# packmonitor.net
KiCad netlist of a schematic drawn in EAGLE
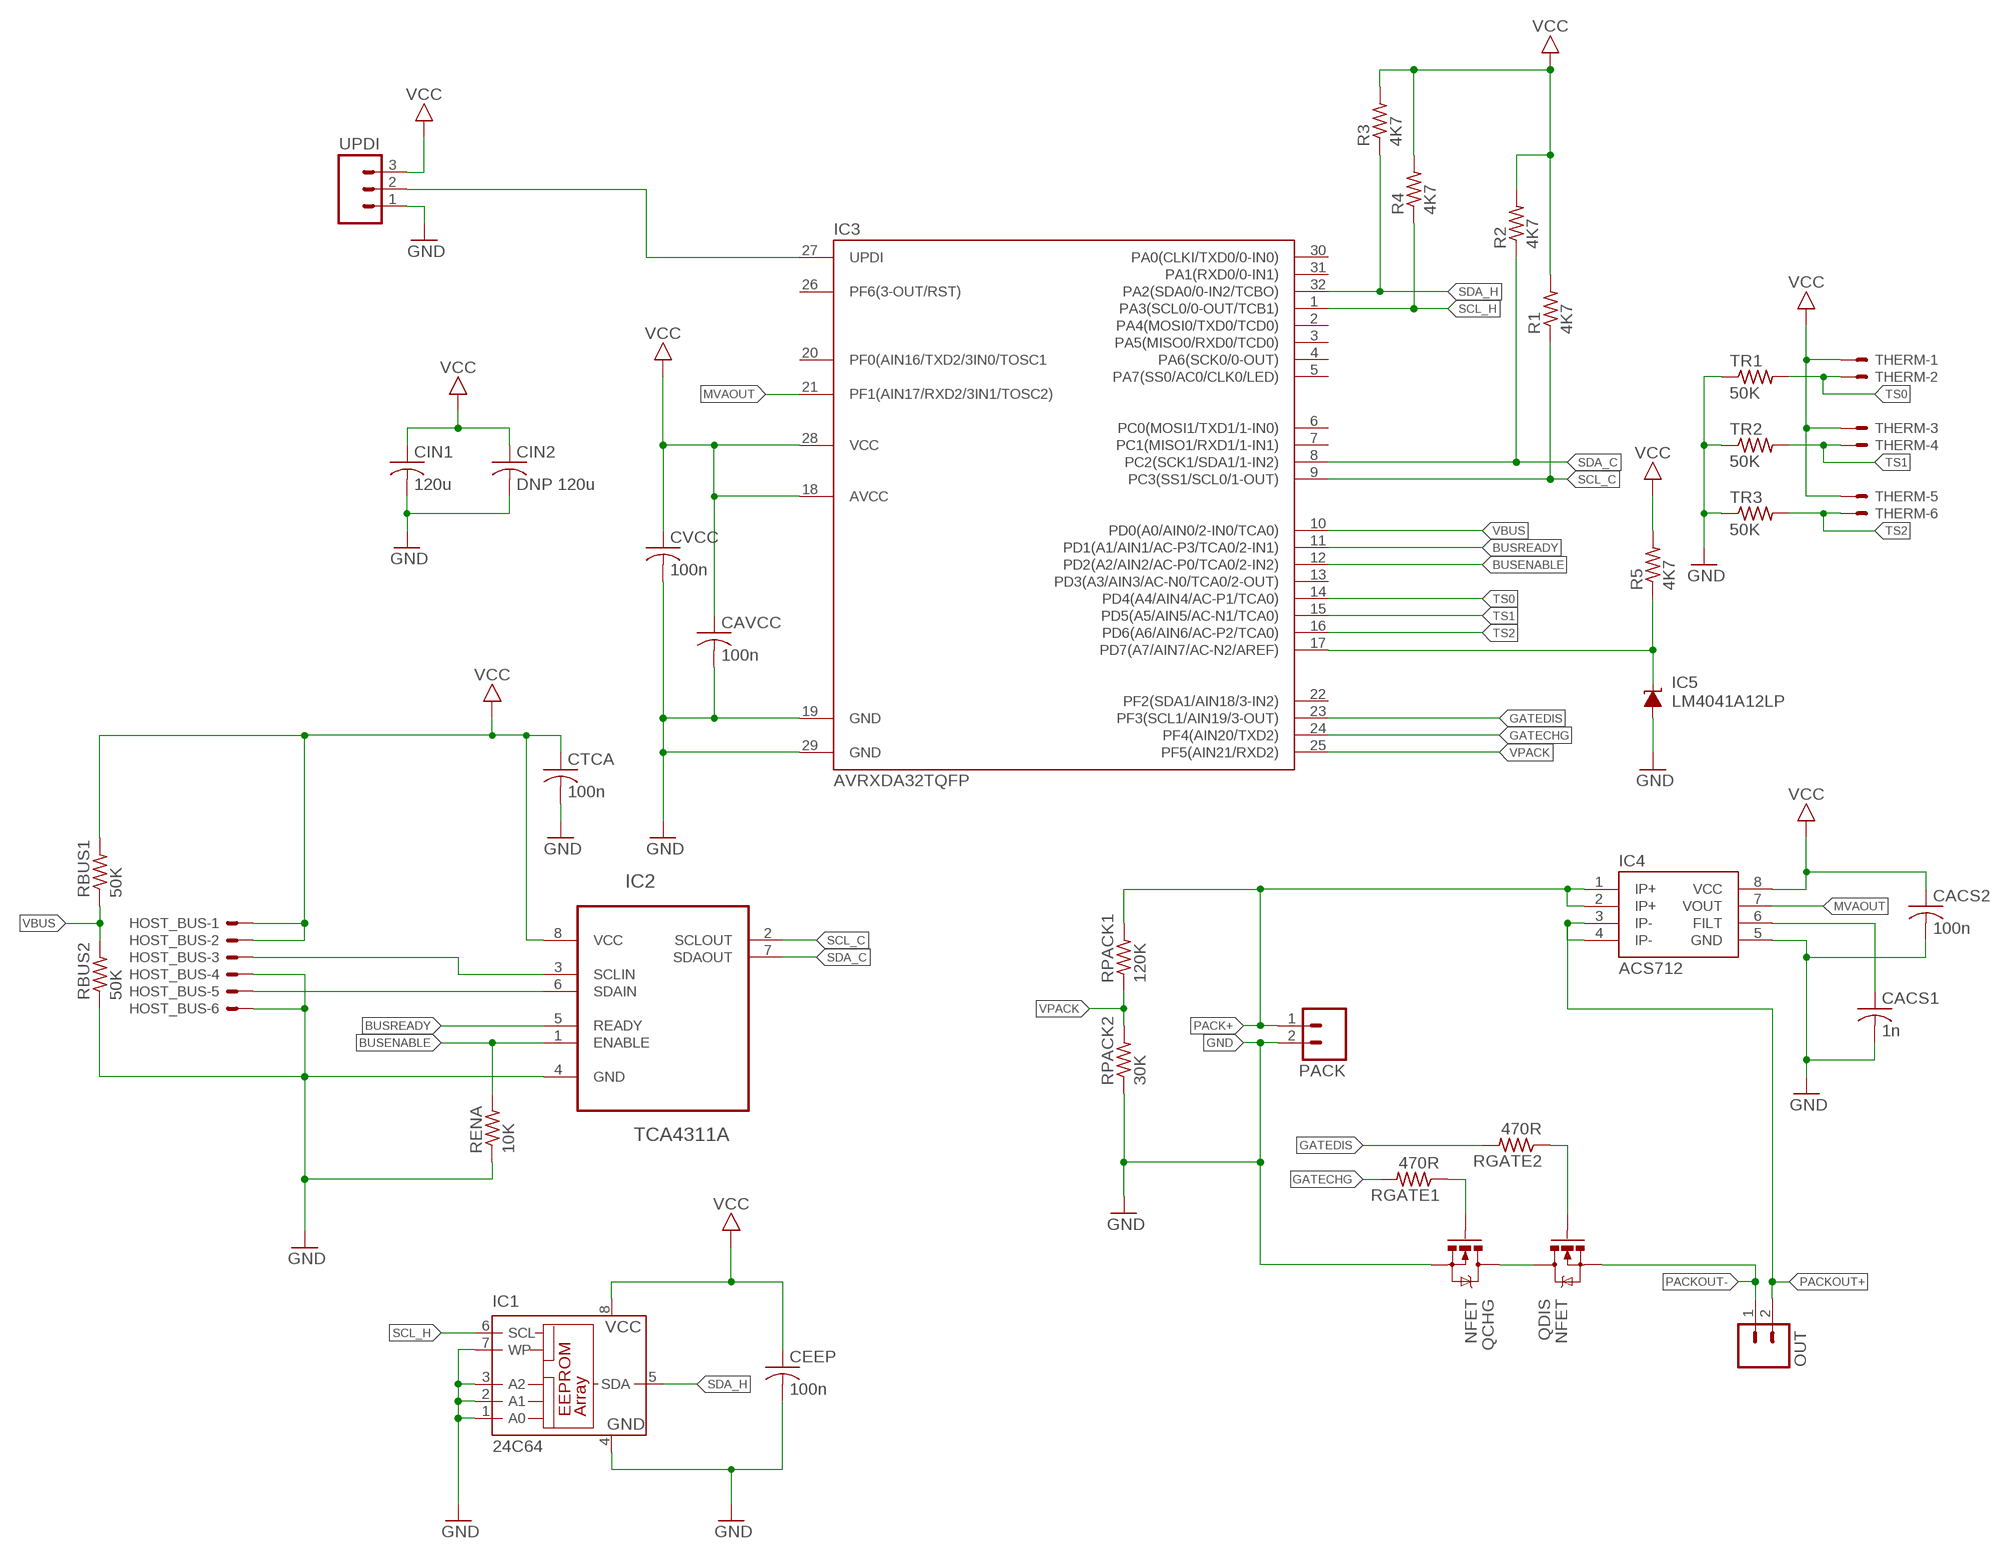
[diagram p0: schematic, sheet 1]

(export (version "E")
  (design (tool "Eeschema 10.0.6"))
  (components
    (comp (ref "CACS1")
      (value "1n")
      (footprint "eagle-import:C0603")
      (libsource (lib "eagle-import") (part "C-USC0603"))
    )
    (comp (ref "CACS2")
      (value "100n")
      (footprint "eagle-import:C0603")
      (libsource (lib "eagle-import") (part "C-USC0603"))
    )
    (comp (ref "CAVCC")
      (value "100n")
      (footprint "eagle-import:C0603")
      (libsource (lib "eagle-import") (part "C-USC0603"))
    )
    (comp (ref "CEEP")
      (value "100n")
      (footprint "eagle-import:C0603")
      (libsource (lib "eagle-import") (part "C-USC0603"))
    )
    (comp (ref "CIN1")
      (value "120u")
      (footprint "eagle-import:C1206")
      (libsource (lib "eagle-import") (part "C-USC1206"))
    )
    (comp (ref "CIN2")
      (value "DNP 120u")
      (footprint "eagle-import:C1206")
      (libsource (lib "eagle-import") (part "C-USC1206"))
    )
    (comp (ref "CTCA")
      (value "100n")
      (footprint "eagle-import:C0603")
      (libsource (lib "eagle-import") (part "C-USC0603"))
    )
    (comp (ref "CVCC")
      (value "100n")
      (footprint "eagle-import:C0603")
      (libsource (lib "eagle-import") (part "C-USC0603"))
    )
    (comp (ref "HOST_BUS")
      (value "JST-XH-06-PIN-LONG-PAD")
      (footprint "eagle-import:JST-XH-06-PACKAGE-LONG-PAD")
      (libsource (lib "eagle-import") (part "JST-XH-06-PIN-LONG-PAD"))
    )
    (comp (ref "IC1")
      (value "24C64")
      (footprint "eagle-import:SO-08")
      (libsource (lib "eagle-import") (part "24CSN04C"))
    )
    (comp (ref "IC2")
      (value "TCA4311A")
      (footprint "eagle-import:SOIC127P600X175-8N")
      (fields (field (name "MPN") "PCA9511AD,118"))
      (libsource (lib "eagle-import") (part "PCA9511AD,118"))
    )
    (comp (ref "IC3")
      (value "AVRXDA32TQFP")
      (footprint "eagle-import:TQFP32-08")
      (libsource (lib "eagle-import") (part "AVRXDA32TQFP"))
    )
    (comp (ref "IC4")
      (value "ACS712")
      (footprint "eagle-import:SO08")
      (libsource (lib "eagle-import") (part "ACS712"))
    )
    (comp (ref "IC5")
      (value "LM4041A12LP")
      (footprint "eagle-import:LP_O-PBCY-W3")
      (libsource (lib "eagle-import") (part "LM4041LPA12"))
    )
    (comp (ref "OUT")
      (value "M023.5MM")
      (footprint "eagle-import:SCREWTERMINAL-3.5MM-2")
      (libsource (lib "eagle-import") (part "M023.5MM"))
    )
    (comp (ref "PACK")
      (value "M023.5MM")
      (footprint "eagle-import:SCREWTERMINAL-3.5MM-2")
      (libsource (lib "eagle-import") (part "M023.5MM"))
    )
    (comp (ref "QCHG")
      (value "NFET")
      (footprint "eagle-import:SO08")
      (libsource (lib "eagle-import") (part "MOSFET-NCHANNELFDS6630A"))
    )
    (comp (ref "QDIS")
      (value "NFET")
      (footprint "eagle-import:SO08")
      (libsource (lib "eagle-import") (part "MOSFET-NCHANNELFDS6630A"))
    )
    (comp (ref "R1")
      (value "4K7")
      (footprint "eagle-import:R0603")
      (libsource (lib "eagle-import") (part "R-US_R0603"))
    )
    (comp (ref "R2")
      (value "4K7")
      (footprint "eagle-import:R0603")
      (libsource (lib "eagle-import") (part "R-US_R0603"))
    )
    (comp (ref "R3")
      (value "4K7")
      (footprint "eagle-import:R0603")
      (libsource (lib "eagle-import") (part "R-US_R0603"))
    )
    (comp (ref "R4")
      (value "4K7")
      (footprint "eagle-import:R0603")
      (libsource (lib "eagle-import") (part "R-US_R0603"))
    )
    (comp (ref "R5")
      (value "4K7")
      (footprint "eagle-import:R0603")
      (libsource (lib "eagle-import") (part "R-US_R0603"))
    )
    (comp (ref "RBUS1")
      (value "50K")
      (footprint "eagle-import:R0805")
      (libsource (lib "eagle-import") (part "R-US_R0805"))
    )
    (comp (ref "RBUS2")
      (value "50K")
      (footprint "eagle-import:R0805")
      (libsource (lib "eagle-import") (part "R-US_R0805"))
    )
    (comp (ref "RENA")
      (value "10K")
      (footprint "eagle-import:R0603")
      (libsource (lib "eagle-import") (part "R-US_R0603"))
    )
    (comp (ref "RGATE1")
      (value "470R")
      (footprint "eagle-import:R0603")
      (libsource (lib "eagle-import") (part "R-US_R0603"))
    )
    (comp (ref "RGATE2")
      (value "470R")
      (footprint "eagle-import:R0603")
      (libsource (lib "eagle-import") (part "R-US_R0603"))
    )
    (comp (ref "RPACK1")
      (value "120K")
      (footprint "eagle-import:R0805")
      (libsource (lib "eagle-import") (part "R-US_R0805"))
    )
    (comp (ref "RPACK2")
      (value "30K")
      (footprint "eagle-import:R0805")
      (libsource (lib "eagle-import") (part "R-US_R0805"))
    )
    (comp (ref "THERM")
      (value "JST-XH-06-PIN-ROUND-PAD")
      (footprint "eagle-import:JST-XH-06-PACKAGE-ROUND-PAD")
      (libsource (lib "eagle-import") (part "JST-XH-06-PIN-ROUND-PAD"))
    )
    (comp (ref "TR1")
      (value "50K")
      (footprint "eagle-import:R0805")
      (libsource (lib "eagle-import") (part "R-US_R0805"))
    )
    (comp (ref "TR2")
      (value "50K")
      (footprint "eagle-import:R0805")
      (libsource (lib "eagle-import") (part "R-US_R0805"))
    )
    (comp (ref "TR3")
      (value "50K")
      (footprint "eagle-import:R0805")
      (libsource (lib "eagle-import") (part "R-US_R0805"))
    )
    (comp (ref "UPDI")
      (value "M03PTH")
      (footprint "eagle-import:1X03")
      (libsource (lib "eagle-import") (part "M03PTH"))
    )
  )
  (nets
    (net (code "1") (name "BUSENABLE") (class "Default")
      (node (ref "IC2") (pin "1") (pinfunction "ENABLE_1") (pintype "input"))
      (node (ref "IC3") (pin "12") (pinfunction "PD2(A2/AIN2/AC-P0/TCA0/2-IN2)_12") (pintype "bidirectional"))
      (node (ref "RENA") (pin "2") (pinfunction "2_2") (pintype "passive"))
    )
    (net (code "2") (name "BUSREADY") (class "Default")
      (node (ref "IC2") (pin "5") (pinfunction "READY_5") (pintype "input"))
      (node (ref "IC3") (pin "11") (pinfunction "PD1(A1/AIN1/AC-P3/TCA0/2-IN1)_11") (pintype "bidirectional"))
    )
    (net (code "3") (name "GATECHG") (class "Default")
      (node (ref "IC3") (pin "24") (pinfunction "PF4(AIN20/TXD2)_24") (pintype "bidirectional"))
      (node (ref "RGATE1") (pin "2") (pinfunction "2_2") (pintype "passive"))
    )
    (net (code "4") (name "GATEDIS") (class "Default")
      (node (ref "IC3") (pin "23") (pinfunction "PF3(SCL1/AIN19/3-OUT)_23") (pintype "bidirectional"))
      (node (ref "RGATE2") (pin "2") (pinfunction "2_2") (pintype "passive"))
    )
    (net (code "5") (name "GND") (class "Default")
      (node (ref "CACS1") (pin "2") (pinfunction "2_2") (pintype "passive"))
      (node (ref "CACS2") (pin "2") (pinfunction "2_2") (pintype "passive"))
      (node (ref "CAVCC") (pin "2") (pinfunction "2_2") (pintype "passive"))
      (node (ref "CEEP") (pin "2") (pinfunction "2_2") (pintype "passive"))
      (node (ref "CIN1") (pin "2") (pinfunction "2_2") (pintype "passive"))
      (node (ref "CIN2") (pin "2") (pinfunction "2_2") (pintype "passive"))
      (node (ref "CTCA") (pin "2") (pinfunction "2_2") (pintype "passive"))
      (node (ref "CVCC") (pin "2") (pinfunction "2_2") (pintype "passive"))
      (node (ref "HOST_BUS") (pin "4") (pinfunction "S_4") (pintype "passive"))
      (node (ref "HOST_BUS") (pin "6") (pinfunction "S_6") (pintype "passive"))
      (node (ref "IC1") (pin "1") (pinfunction "A0_1") (pintype "input"))
      (node (ref "IC1") (pin "2") (pinfunction "A1_2") (pintype "input"))
      (node (ref "IC1") (pin "3") (pinfunction "A2_3") (pintype "input"))
      (node (ref "IC1") (pin "4") (pinfunction "GND_4") (pintype "power_in"))
      (node (ref "IC1") (pin "7") (pinfunction "WP_7") (pintype "input"))
      (node (ref "IC2") (pin "4") (pinfunction "GND_4") (pintype "passive"))
      (node (ref "IC3") (pin "19") (pinfunction "GND_19") (pintype "power_in"))
      (node (ref "IC3") (pin "29") (pinfunction "GND_29") (pintype "power_in"))
      (node (ref "IC4") (pin "5") (pinfunction "GND_5") (pintype "bidirectional"))
      (node (ref "IC5") (pin "3") (pinfunction "A_3") (pintype "passive"))
      (node (ref "PACK") (pin "2") (pinfunction "2_2") (pintype "passive"))
      (node (ref "QCHG") (pin "1") (pinfunction "S_1") (pintype "passive"))
      (node (ref "QCHG") (pin "2") (pinfunction "S_2") (pintype "passive"))
      (node (ref "QCHG") (pin "3") (pinfunction "S_3") (pintype "passive"))
      (node (ref "RBUS2") (pin "1") (pinfunction "1_1") (pintype "passive"))
      (node (ref "RENA") (pin "1") (pinfunction "1_1") (pintype "passive"))
      (node (ref "RPACK2") (pin "1") (pinfunction "1_1") (pintype "passive"))
      (node (ref "TR1") (pin "1") (pinfunction "1_1") (pintype "passive"))
      (node (ref "TR2") (pin "1") (pinfunction "1_1") (pintype "passive"))
      (node (ref "TR3") (pin "1") (pinfunction "1_1") (pintype "passive"))
      (node (ref "UPDI") (pin "1") (pinfunction "1_1") (pintype "passive"))
    )
    (net (code "6") (name "MVAOUT") (class "Default")
      (node (ref "IC3") (pin "21") (pinfunction "PF1(AIN17/RXD2/3IN1/TOSC2)_21") (pintype "bidirectional"))
      (node (ref "IC4") (pin "7") (pinfunction "VOUT_7") (pintype "bidirectional"))
    )
    (net (code "7") (name "Net-(HOST_BUSC-S)") (class "Default")
      (node (ref "HOST_BUS") (pin "3") (pinfunction "S_3") (pintype "passive"))
      (node (ref "IC2") (pin "3") (pinfunction "SCLIN_3") (pintype "input"))
    )
    (net (code "8") (name "Net-(HOST_BUSE-S)") (class "Default")
      (node (ref "HOST_BUS") (pin "5") (pinfunction "S_5") (pintype "passive"))
      (node (ref "IC2") (pin "6") (pinfunction "SDAIN_6") (pintype "input"))
    )
    (net (code "9") (name "Net-(IC3-PD7(A7{slash}AIN7{slash}AC-N2{slash}AREF))") (class "Default")
      (node (ref "IC3") (pin "17") (pinfunction "PD7(A7/AIN7/AC-N2/AREF)_17") (pintype "bidirectional"))
      (node (ref "IC5") (pin "2") (pinfunction "C_2") (pintype "passive"))
      (node (ref "R5") (pin "1") (pinfunction "1_1") (pintype "passive"))
    )
    (net (code "10") (name "Net-(IC3-UPDI)") (class "Default")
      (node (ref "IC3") (pin "27") (pinfunction "UPDI_27") (pintype "bidirectional"))
      (node (ref "UPDI") (pin "2") (pinfunction "2_2") (pintype "passive"))
    )
    (net (code "11") (name "Net-(IC4-FILT)") (class "Default")
      (node (ref "CACS1") (pin "1") (pinfunction "1_1") (pintype "passive"))
      (node (ref "IC4") (pin "6") (pinfunction "FILT_6") (pintype "bidirectional"))
    )
    (net (code "12") (name "Net-(QCHG-D-Pad5)") (class "Default")
      (node (ref "QCHG") (pin "5") (pinfunction "D_5") (pintype "passive"))
      (node (ref "QCHG") (pin "6") (pinfunction "D_6") (pintype "passive"))
      (node (ref "QCHG") (pin "7") (pinfunction "D_7") (pintype "passive"))
      (node (ref "QCHG") (pin "8") (pinfunction "D_8") (pintype "passive"))
      (node (ref "QDIS") (pin "5") (pinfunction "D_5") (pintype "passive"))
      (node (ref "QDIS") (pin "6") (pinfunction "D_6") (pintype "passive"))
      (node (ref "QDIS") (pin "7") (pinfunction "D_7") (pintype "passive"))
      (node (ref "QDIS") (pin "8") (pinfunction "D_8") (pintype "passive"))
    )
    (net (code "13") (name "Net-(QCHG-G)") (class "Default")
      (node (ref "QCHG") (pin "4") (pinfunction "G_4") (pintype "passive"))
      (node (ref "RGATE1") (pin "1") (pinfunction "1_1") (pintype "passive"))
    )
    (net (code "14") (name "Net-(QDIS-G)") (class "Default")
      (node (ref "QDIS") (pin "4") (pinfunction "G_4") (pintype "passive"))
      (node (ref "RGATE2") (pin "1") (pinfunction "1_1") (pintype "passive"))
    )
    (net (code "15") (name "PACK+") (class "Default")
      (node (ref "IC4") (pin "1") (pinfunction "IP+_1") (pintype "bidirectional"))
      (node (ref "IC4") (pin "2") (pinfunction "IP+_2") (pintype "bidirectional"))
      (node (ref "PACK") (pin "1") (pinfunction "1_1") (pintype "passive"))
      (node (ref "RPACK1") (pin "2") (pinfunction "2_2") (pintype "passive"))
    )
    (net (code "16") (name "PACKOUT+") (class "Default")
      (node (ref "IC4") (pin "3") (pinfunction "IP-_3") (pintype "bidirectional"))
      (node (ref "IC4") (pin "4") (pinfunction "IP-_4") (pintype "bidirectional"))
      (node (ref "OUT") (pin "2") (pinfunction "2_2") (pintype "passive"))
    )
    (net (code "17") (name "PACKOUT-") (class "Default")
      (node (ref "OUT") (pin "1") (pinfunction "1_1") (pintype "passive"))
      (node (ref "QDIS") (pin "1") (pinfunction "S_1") (pintype "passive"))
      (node (ref "QDIS") (pin "2") (pinfunction "S_2") (pintype "passive"))
      (node (ref "QDIS") (pin "3") (pinfunction "S_3") (pintype "passive"))
    )
    (net (code "18") (name "SCL_C") (class "Default")
      (node (ref "IC2") (pin "2") (pinfunction "SCLOUT_2") (pintype "output"))
      (node (ref "IC3") (pin "9") (pinfunction "PC3(SS1/SCL0/1-OUT)_9") (pintype "bidirectional"))
      (node (ref "R1") (pin "1") (pinfunction "1_1") (pintype "passive"))
    )
    (net (code "19") (name "SCL_H") (class "Default")
      (node (ref "IC1") (pin "6") (pinfunction "SCL_6") (pintype "input"))
      (node (ref "IC3") (pin "1") (pinfunction "PA3(SCL0/0-OUT/TCB1)_1") (pintype "bidirectional"))
      (node (ref "R4") (pin "1") (pinfunction "1_1") (pintype "passive"))
    )
    (net (code "20") (name "SDA_C") (class "Default")
      (node (ref "IC2") (pin "7") (pinfunction "SDAOUT_7") (pintype "output"))
      (node (ref "IC3") (pin "8") (pinfunction "PC2(SCK1/SDA1/1-IN2)_8") (pintype "bidirectional"))
      (node (ref "R2") (pin "1") (pinfunction "1_1") (pintype "passive"))
    )
    (net (code "21") (name "SDA_H") (class "Default")
      (node (ref "IC1") (pin "5") (pinfunction "SDA_5") (pintype "bidirectional"))
      (node (ref "IC3") (pin "32") (pinfunction "PA2(SDA0/0-IN2/TCBO)_32") (pintype "bidirectional"))
      (node (ref "R3") (pin "1") (pinfunction "1_1") (pintype "passive"))
    )
    (net (code "22") (name "TS0") (class "Default")
      (node (ref "IC3") (pin "14") (pinfunction "PD4(A4/AIN4/AC-P1/TCA0)_14") (pintype "bidirectional"))
      (node (ref "THERM") (pin "2") (pinfunction "S_2") (pintype "passive"))
      (node (ref "TR1") (pin "2") (pinfunction "2_2") (pintype "passive"))
    )
    (net (code "23") (name "TS1") (class "Default")
      (node (ref "IC3") (pin "15") (pinfunction "PD5(A5/AIN5/AC-N1/TCA0)_15") (pintype "bidirectional"))
      (node (ref "THERM") (pin "4") (pinfunction "S_4") (pintype "passive"))
      (node (ref "TR2") (pin "2") (pinfunction "2_2") (pintype "passive"))
    )
    (net (code "24") (name "TS2") (class "Default")
      (node (ref "IC3") (pin "16") (pinfunction "PD6(A6/AIN6/AC-P2/TCA0)_16") (pintype "bidirectional"))
      (node (ref "THERM") (pin "6") (pinfunction "S_6") (pintype "passive"))
      (node (ref "TR3") (pin "2") (pinfunction "2_2") (pintype "passive"))
    )
    (net (code "25") (name "VBUS") (class "Default")
      (node (ref "IC3") (pin "10") (pinfunction "PD0(A0/AIN0/2-IN0/TCA0)_10") (pintype "bidirectional"))
      (node (ref "RBUS1") (pin "1") (pinfunction "1_1") (pintype "passive"))
      (node (ref "RBUS2") (pin "2") (pinfunction "2_2") (pintype "passive"))
    )
    (net (code "26") (name "VCC") (class "Default")
      (node (ref "CACS2") (pin "1") (pinfunction "1_1") (pintype "passive"))
      (node (ref "CAVCC") (pin "1") (pinfunction "1_1") (pintype "passive"))
      (node (ref "CEEP") (pin "1") (pinfunction "1_1") (pintype "passive"))
      (node (ref "CIN1") (pin "1") (pinfunction "1_1") (pintype "passive"))
      (node (ref "CIN2") (pin "1") (pinfunction "1_1") (pintype "passive"))
      (node (ref "CTCA") (pin "1") (pinfunction "1_1") (pintype "passive"))
      (node (ref "CVCC") (pin "1") (pinfunction "1_1") (pintype "passive"))
      (node (ref "HOST_BUS") (pin "1") (pinfunction "S_1") (pintype "passive"))
      (node (ref "HOST_BUS") (pin "2") (pinfunction "S_2") (pintype "passive"))
      (node (ref "IC1") (pin "8") (pinfunction "VCC_8") (pintype "power_in"))
      (node (ref "IC2") (pin "8") (pinfunction "VCC_8") (pintype "power_in"))
      (node (ref "IC3") (pin "18") (pinfunction "AVCC_18") (pintype "passive"))
      (node (ref "IC3") (pin "28") (pinfunction "VCC_28") (pintype "power_in"))
      (node (ref "IC4") (pin "8") (pinfunction "VCC_8") (pintype "bidirectional"))
      (node (ref "R1") (pin "2") (pinfunction "2_2") (pintype "passive"))
      (node (ref "R2") (pin "2") (pinfunction "2_2") (pintype "passive"))
      (node (ref "R3") (pin "2") (pinfunction "2_2") (pintype "passive"))
      (node (ref "R4") (pin "2") (pinfunction "2_2") (pintype "passive"))
      (node (ref "R5") (pin "2") (pinfunction "2_2") (pintype "passive"))
      (node (ref "RBUS1") (pin "2") (pinfunction "2_2") (pintype "passive"))
      (node (ref "THERM") (pin "1") (pinfunction "S_1") (pintype "passive"))
      (node (ref "THERM") (pin "3") (pinfunction "S_3") (pintype "passive"))
      (node (ref "THERM") (pin "5") (pinfunction "S_5") (pintype "passive"))
      (node (ref "UPDI") (pin "3") (pinfunction "3_3") (pintype "passive"))
    )
    (net (code "27") (name "VPACK") (class "Default")
      (node (ref "IC3") (pin "25") (pinfunction "PF5(AIN21/RXD2)_25") (pintype "bidirectional"))
      (node (ref "RPACK1") (pin "1") (pinfunction "1_1") (pintype "passive"))
      (node (ref "RPACK2") (pin "2") (pinfunction "2_2") (pintype "passive"))
    )
    (net (code "28") (name "unconnected-(IC3-PA0(CLKI{slash}TXD0{slash}0-IN0)-Pad30)") (class "Default")
      (node (ref "IC3") (pin "30") (pinfunction "PA0(CLKI/TXD0/0-IN0)_30") (pintype "bidirectional"))
    )
    (net (code "29") (name "unconnected-(IC3-PA1(RXD0{slash}0-IN1)-Pad31)") (class "Default")
      (node (ref "IC3") (pin "31") (pinfunction "PA1(RXD0/0-IN1)_31") (pintype "bidirectional"))
    )
    (net (code "30") (name "unconnected-(IC3-PA4(MOSI0{slash}TXD0{slash}TCD0)-Pad2)") (class "Default")
      (node (ref "IC3") (pin "2") (pinfunction "PA4(MOSI0/TXD0/TCD0)_2") (pintype "bidirectional"))
    )
    (net (code "31") (name "unconnected-(IC3-PA5(MISO0{slash}RXD0{slash}TCD0)-Pad3)") (class "Default")
      (node (ref "IC3") (pin "3") (pinfunction "PA5(MISO0/RXD0/TCD0)_3") (pintype "bidirectional"))
    )
    (net (code "32") (name "unconnected-(IC3-PA6(SCK0{slash}0-OUT)-Pad4)") (class "Default")
      (node (ref "IC3") (pin "4") (pinfunction "PA6(SCK0/0-OUT)_4") (pintype "bidirectional"))
    )
    (net (code "33") (name "unconnected-(IC3-PA7(SS0{slash}AC0{slash}CLK0{slash}LED)-Pad5)") (class "Default")
      (node (ref "IC3") (pin "5") (pinfunction "PA7(SS0/AC0/CLK0/LED)_5") (pintype "bidirectional"))
    )
    (net (code "34") (name "unconnected-(IC3-PC0(MOSI1{slash}TXD1{slash}1-IN0)-Pad6)") (class "Default")
      (node (ref "IC3") (pin "6") (pinfunction "PC0(MOSI1/TXD1/1-IN0)_6") (pintype "bidirectional"))
    )
    (net (code "35") (name "unconnected-(IC3-PC1(MISO1{slash}RXD1{slash}1-IN1)-Pad7)") (class "Default")
      (node (ref "IC3") (pin "7") (pinfunction "PC1(MISO1/RXD1/1-IN1)_7") (pintype "bidirectional"))
    )
    (net (code "36") (name "unconnected-(IC3-PD3(A3{slash}AIN3{slash}AC-N0{slash}TCA0{slash}2-OUT)-Pad13)") (class "Default")
      (node (ref "IC3") (pin "13") (pinfunction "PD3(A3/AIN3/AC-N0/TCA0/2-OUT)_13") (pintype "bidirectional"))
    )
    (net (code "37") (name "unconnected-(IC3-PF0(AIN16{slash}TXD2{slash}3IN0{slash}TOSC1-Pad20)") (class "Default")
      (node (ref "IC3") (pin "20") (pinfunction "PF0(AIN16/TXD2/3IN0/TOSC1_20") (pintype "bidirectional"))
    )
    (net (code "38") (name "unconnected-(IC3-PF2(SDA1{slash}AIN18{slash}3-IN2)-Pad22)") (class "Default")
      (node (ref "IC3") (pin "22") (pinfunction "PF2(SDA1/AIN18/3-IN2)_22") (pintype "bidirectional"))
    )
    (net (code "39") (name "unconnected-(IC3-PF6(3-OUT{slash}RST)-Pad26)") (class "Default")
      (node (ref "IC3") (pin "26") (pinfunction "PF6(3-OUT/RST)_26") (pintype "bidirectional"))
    )
  )
)
